# dsky_md_2_3v.net
KiCad netlist of a schematic drawn in EAGLE
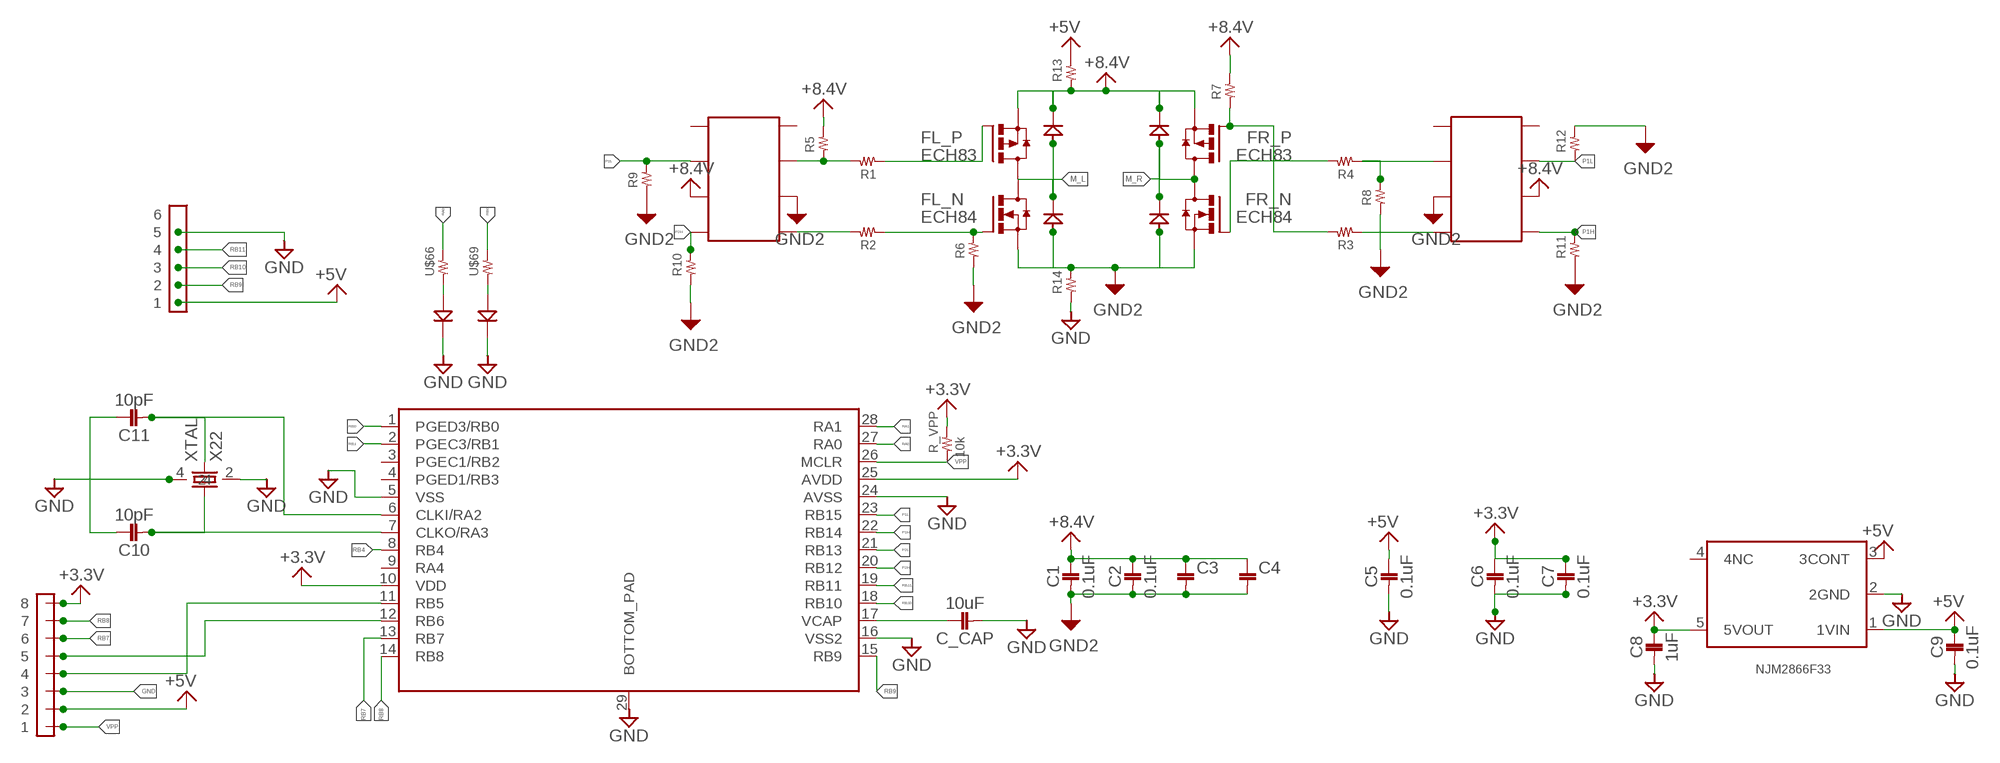
[diagram p0: schematic, sheet 1]

(export (version "E")
  (design (tool "Eeschema 10.0.6"))
  (components
    (comp (ref "C1")
      (value "0.1uF")
      (footprint "eagle-import:1608")
      (libsource (lib "eagle-import") (part "1608"))
    )
    (comp (ref "C2")
      (value "0.1uF")
      (footprint "eagle-import:1608")
      (libsource (lib "eagle-import") (part "1608"))
    )
    (comp (ref "C3")
      (value "2012")
      (footprint "eagle-import:2012")
      (libsource (lib "eagle-import") (part "2012"))
    )
    (comp (ref "C4")
      (value "2012")
      (footprint "eagle-import:2012")
      (libsource (lib "eagle-import") (part "2012"))
    )
    (comp (ref "C5")
      (value "0.1uF")
      (footprint "eagle-import:1608")
      (libsource (lib "eagle-import") (part "1608"))
    )
    (comp (ref "C6")
      (value "0.1uF")
      (footprint "eagle-import:1608")
      (libsource (lib "eagle-import") (part "1608"))
    )
    (comp (ref "C7")
      (value "0.1uF")
      (footprint "eagle-import:1608")
      (libsource (lib "eagle-import") (part "1608"))
    )
    (comp (ref "C8")
      (value "1uF")
      (footprint "eagle-import:1608")
      (libsource (lib "eagle-import") (part "1608"))
    )
    (comp (ref "C9")
      (value "0.1uF")
      (footprint "eagle-import:1608")
      (libsource (lib "eagle-import") (part "1608"))
    )
    (comp (ref "C10")
      (value "10pF")
      (footprint "eagle-import:1608")
      (libsource (lib "eagle-import") (part "1608"))
    )
    (comp (ref "C11")
      (value "10pF")
      (footprint "eagle-import:1608")
      (libsource (lib "eagle-import") (part "1608"))
    )
    (comp (ref "C_CAP")
      (value "10uF")
      (footprint "eagle-import:1608")
      (libsource (lib "eagle-import") (part "1608"))
    )
    (comp (ref "FL_N")
      (value "ECH84")
      (footprint "eagle-import:ECH8")
      (libsource (lib "eagle-import") (part "ECH84"))
    )
    (comp (ref "FL_P")
      (value "ECH83")
      (footprint "eagle-import:ECH8")
      (libsource (lib "eagle-import") (part "ECH83"))
    )
    (comp (ref "FR_N")
      (value "ECH84")
      (footprint "eagle-import:ECH8")
      (libsource (lib "eagle-import") (part "ECH84"))
    )
    (comp (ref "FR_P")
      (value "ECH83")
      (footprint "eagle-import:ECH8")
      (libsource (lib "eagle-import") (part "ECH83"))
    )
    (comp (ref "IC_L")
      (value "TC1427COA")
      (footprint "eagle-import:SOIC8")
      (libsource (lib "eagle-import") (part "TC1427COA"))
    )
    (comp (ref "IC_R")
      (value "TC1427COA")
      (footprint "eagle-import:SOIC8")
      (libsource (lib "eagle-import") (part "TC1427COA"))
    )
    (comp (ref "NJM2866F33")
      (value "TAR5SB")
      (footprint "eagle-import:SSOP5-P-0.95")
      (libsource (lib "eagle-import") (part "TAR5SB"))
    )
    (comp (ref "R1")
      (value "RESISTOR__SMD")
      (footprint "eagle-import:1608")
      (libsource (lib "eagle-import") (part "RESISTOR__SMD"))
    )
    (comp (ref "R2")
      (value "RESISTOR__SMD")
      (footprint "eagle-import:1608")
      (libsource (lib "eagle-import") (part "RESISTOR__SMD"))
    )
    (comp (ref "R3")
      (value "RESISTOR__SMD")
      (footprint "eagle-import:1608")
      (libsource (lib "eagle-import") (part "RESISTOR__SMD"))
    )
    (comp (ref "R4")
      (value "RESISTOR__SMD")
      (footprint "eagle-import:1608")
      (libsource (lib "eagle-import") (part "RESISTOR__SMD"))
    )
    (comp (ref "R5")
      (value "RESISTOR__SMD")
      (footprint "eagle-import:1608")
      (libsource (lib "eagle-import") (part "RESISTOR__SMD"))
    )
    (comp (ref "R6")
      (value "RESISTOR__SMD")
      (footprint "eagle-import:1608")
      (libsource (lib "eagle-import") (part "RESISTOR__SMD"))
    )
    (comp (ref "R7")
      (value "RESISTOR__SMD")
      (footprint "eagle-import:1608")
      (libsource (lib "eagle-import") (part "RESISTOR__SMD"))
    )
    (comp (ref "R8")
      (value "RESISTOR__SMD")
      (footprint "eagle-import:1608")
      (libsource (lib "eagle-import") (part "RESISTOR__SMD"))
    )
    (comp (ref "R9")
      (value "RESISTOR__SMD")
      (footprint "eagle-import:1608")
      (libsource (lib "eagle-import") (part "RESISTOR__SMD"))
    )
    (comp (ref "R10")
      (value "RESISTOR__SMD")
      (footprint "eagle-import:1608")
      (libsource (lib "eagle-import") (part "RESISTOR__SMD"))
    )
    (comp (ref "R11")
      (value "RESISTOR__SMD")
      (footprint "eagle-import:1608")
      (libsource (lib "eagle-import") (part "RESISTOR__SMD"))
    )
    (comp (ref "R12")
      (value "RESISTOR__SMD")
      (footprint "eagle-import:1608")
      (libsource (lib "eagle-import") (part "RESISTOR__SMD"))
    )
    (comp (ref "R13")
      (value "RESISTOR__SMD")
      (footprint "eagle-import:1608")
      (libsource (lib "eagle-import") (part "RESISTOR__SMD"))
    )
    (comp (ref "R14")
      (value "RESISTOR__SMD")
      (footprint "eagle-import:1608")
      (libsource (lib "eagle-import") (part "RESISTOR__SMD"))
    )
    (comp (ref "R_VPP")
      (value "10k")
      (footprint "eagle-import:1608")
      (libsource (lib "eagle-import") (part "RESISTOR__SMD"))
    )
    (comp (ref "U$3")
      (value "SS2040")
      (footprint "eagle-import:SOD-123FL")
      (libsource (lib "eagle-import") (part "SS2040"))
    )
    (comp (ref "U$5")
      (value "DSPIC33EP32MC202")
      (footprint "eagle-import:QFN-S28_6X6MC")
      (libsource (lib "eagle-import") (part "DSPIC33EP32MC202"))
    )
    (comp (ref "U$6")
      (value "1608")
      (footprint "eagle-import:1608")
      (libsource (lib "eagle-import") (part "LED_1608"))
    )
    (comp (ref "U$16")
      (value "1608")
      (footprint "eagle-import:1608")
      (libsource (lib "eagle-import") (part "LED_1608"))
    )
    (comp (ref "U$44")
      (value "FH12-6S-0.5")
      (footprint "eagle-import:FPC6")
      (libsource (lib "eagle-import") (part "FH12-6S-0.5"))
    )
    (comp (ref "U$66")
      (value "RESISTOR__SMD")
      (footprint "eagle-import:1608")
      (libsource (lib "eagle-import") (part "RESISTOR__SMD"))
    )
    (comp (ref "U$69")
      (value "RESISTOR__SMD")
      (footprint "eagle-import:1608")
      (libsource (lib "eagle-import") (part "RESISTOR__SMD"))
    )
    (comp (ref "U$70")
      (value "SS2040")
      (footprint "eagle-import:SOD-123FL")
      (libsource (lib "eagle-import") (part "SS2040"))
    )
    (comp (ref "U$71")
      (value "SS2040")
      (footprint "eagle-import:SOD-123FL")
      (libsource (lib "eagle-import") (part "SS2040"))
    )
    (comp (ref "U$73")
      (value "SS2040")
      (footprint "eagle-import:SOD-123FL")
      (libsource (lib "eagle-import") (part "SS2040"))
    )
    (comp (ref "U$80")
      (value "PIN_HEADER_8")
      (footprint "eagle-import:PIN_HEADER_8")
      (libsource (lib "eagle-import") (part "PIN_HEADER_8"))
    )
    (comp (ref "XTAL")
      (value "X22")
      (footprint "eagle-import:SMD_X22")
      (libsource (lib "eagle-import") (part "X22"))
    )
  )
  (nets
    (net (code "1") (name "+3.3V") (class "Default")
      (node (ref "C6") (pin "P$1") (pinfunction "1_P$1") (pintype "passive"))
      (node (ref "C7") (pin "P$1") (pinfunction "1_P$1") (pintype "passive"))
      (node (ref "C8") (pin "P$1") (pinfunction "1_P$1") (pintype "passive"))
      (node (ref "NJM2866F33") (pin "5") (pinfunction "5VOUT_5") (pintype "bidirectional"))
      (node (ref "R_VPP") (pin "2") (pinfunction "P$2_2") (pintype "passive"))
      (node (ref "U$5") (pin "10") (pinfunction "VDD_10") (pintype "bidirectional"))
      (node (ref "U$5") (pin "25") (pinfunction "AVDD_25") (pintype "bidirectional"))
      (node (ref "U$80") (pin "8") (pinfunction "8_8") (pintype "bidirectional"))
    )
    (net (code "2") (name "+5V") (class "Default")
      (node (ref "C5") (pin "P$1") (pinfunction "1_P$1") (pintype "passive"))
      (node (ref "C9") (pin "P$1") (pinfunction "1_P$1") (pintype "passive"))
      (node (ref "NJM2866F33") (pin "1") (pinfunction "1VIN_1") (pintype "bidirectional"))
      (node (ref "NJM2866F33") (pin "3") (pinfunction "3CONT_3") (pintype "bidirectional"))
      (node (ref "R13") (pin "2") (pinfunction "P$2_2") (pintype "passive"))
      (node (ref "U$44") (pin "P1") (pinfunction "1_P1") (pintype "bidirectional"))
      (node (ref "U$80") (pin "2") (pinfunction "2_2") (pintype "bidirectional"))
    )
    (net (code "3") (name "+8.4V") (class "Default")
      (node (ref "C1") (pin "P$1") (pinfunction "1_P$1") (pintype "passive"))
      (node (ref "C2") (pin "P$1") (pinfunction "1_P$1") (pintype "passive"))
      (node (ref "C3") (pin "1") (pinfunction "1_1") (pintype "passive"))
      (node (ref "C4") (pin "1") (pinfunction "1_1") (pintype "passive"))
      (node (ref "FL_P") (pin "1") (pinfunction "S_1") (pintype "passive"))
      (node (ref "FL_P") (pin "2") (pinfunction "S_2") (pintype "passive"))
      (node (ref "FL_P") (pin "3") (pinfunction "S_3") (pintype "passive"))
      (node (ref "FR_P") (pin "1") (pinfunction "S_1") (pintype "passive"))
      (node (ref "FR_P") (pin "2") (pinfunction "S_2") (pintype "passive"))
      (node (ref "FR_P") (pin "3") (pinfunction "S_3") (pintype "passive"))
      (node (ref "IC_L") (pin "3") (pinfunction "3_GND_3") (pintype "bidirectional"))
      (node (ref "IC_R") (pin "3") (pinfunction "3_GND_3") (pintype "bidirectional"))
      (node (ref "R13") (pin "1") (pinfunction "P$1_1") (pintype "passive"))
      (node (ref "R5") (pin "2") (pinfunction "P$2_2") (pintype "passive"))
      (node (ref "R7") (pin "2") (pinfunction "P$2_2") (pintype "passive"))
      (node (ref "U$70") (pin "2") (pinfunction "PK_2") (pintype "bidirectional"))
      (node (ref "U$73") (pin "2") (pinfunction "PK_2") (pintype "bidirectional"))
    )
    (net (code "4") (name "GND") (class "Default")
      (node (ref "C10") (pin "P$1") (pinfunction "1_P$1") (pintype "passive"))
      (node (ref "C11") (pin "P$1") (pinfunction "1_P$1") (pintype "passive"))
      (node (ref "C5") (pin "P$2") (pinfunction "2_P$2") (pintype "passive"))
      (node (ref "C6") (pin "P$2") (pinfunction "2_P$2") (pintype "passive"))
      (node (ref "C7") (pin "P$2") (pinfunction "2_P$2") (pintype "passive"))
      (node (ref "C8") (pin "P$2") (pinfunction "2_P$2") (pintype "passive"))
      (node (ref "C9") (pin "P$2") (pinfunction "2_P$2") (pintype "passive"))
      (node (ref "C_CAP") (pin "P$2") (pinfunction "2_P$2") (pintype "passive"))
      (node (ref "NJM2866F33") (pin "2") (pinfunction "2GND_2") (pintype "bidirectional"))
      (node (ref "R14") (pin "1") (pinfunction "P$1_1") (pintype "passive"))
      (node (ref "U$16") (pin "2") (pinfunction "K_2") (pintype "bidirectional"))
      (node (ref "U$44") (pin "P5") (pinfunction "5_P5") (pintype "bidirectional"))
      (node (ref "U$44") (pin "P_NC1") (pinfunction "5_P_NC1") (pintype "bidirectional"))
      (node (ref "U$44") (pin "P_NC2") (pinfunction "5_P_NC2") (pintype "bidirectional"))
      (node (ref "U$5") (pin "16") (pinfunction "VSS2_16") (pintype "power_in"))
      (node (ref "U$5") (pin "24") (pinfunction "AVSS_24") (pintype "bidirectional"))
      (node (ref "U$5") (pin "29") (pinfunction "BOTTOM_PAD_29") (pintype "bidirectional"))
      (node (ref "U$5") (pin "5") (pinfunction "VSS_5") (pintype "power_in"))
      (node (ref "U$6") (pin "2") (pinfunction "K_2") (pintype "bidirectional"))
      (node (ref "U$80") (pin "3") (pinfunction "3_3") (pintype "bidirectional"))
      (node (ref "XTAL") (pin "2") (pinfunction "2_2") (pintype "bidirectional"))
      (node (ref "XTAL") (pin "4") (pinfunction "4_4") (pintype "bidirectional"))
    )
    (net (code "5") (name "GND2") (class "Default")
      (node (ref "C1") (pin "P$2") (pinfunction "2_P$2") (pintype "passive"))
      (node (ref "C2") (pin "P$2") (pinfunction "2_P$2") (pintype "passive"))
      (node (ref "C3") (pin "2") (pinfunction "2_2") (pintype "passive"))
      (node (ref "C4") (pin "2") (pinfunction "2_2") (pintype "passive"))
      (node (ref "FL_N") (pin "1") (pinfunction "S_1") (pintype "passive"))
      (node (ref "FL_N") (pin "2") (pinfunction "S_2") (pintype "passive"))
      (node (ref "FL_N") (pin "3") (pinfunction "S_3") (pintype "passive"))
      (node (ref "FR_N") (pin "1") (pinfunction "S_1") (pintype "passive"))
      (node (ref "FR_N") (pin "2") (pinfunction "S_2") (pintype "passive"))
      (node (ref "FR_N") (pin "3") (pinfunction "S_3") (pintype "passive"))
      (node (ref "IC_L") (pin "6") (pinfunction "6_VDD_6") (pintype "bidirectional"))
      (node (ref "IC_R") (pin "6") (pinfunction "6_VDD_6") (pintype "bidirectional"))
      (node (ref "R10") (pin "1") (pinfunction "P$1_1") (pintype "passive"))
      (node (ref "R11") (pin "1") (pinfunction "P$1_1") (pintype "passive"))
      (node (ref "R12") (pin "2") (pinfunction "P$2_2") (pintype "passive"))
      (node (ref "R14") (pin "2") (pinfunction "P$2_2") (pintype "passive"))
      (node (ref "R6") (pin "1") (pinfunction "P$1_1") (pintype "passive"))
      (node (ref "R8") (pin "1") (pinfunction "P$1_1") (pintype "passive"))
      (node (ref "R9") (pin "1") (pinfunction "P$1_1") (pintype "passive"))
      (node (ref "U$3") (pin "1") (pinfunction "PA_1") (pintype "bidirectional"))
      (node (ref "U$71") (pin "1") (pinfunction "PA_1") (pintype "bidirectional"))
    )
    (net (code "6") (name "M_L") (class "Default")
      (node (ref "FL_N") (pin "5") (pinfunction "D_5") (pintype "passive"))
      (node (ref "FL_N") (pin "6") (pinfunction "D_6") (pintype "passive"))
      (node (ref "FL_N") (pin "7") (pinfunction "D_7") (pintype "passive"))
      (node (ref "FL_N") (pin "8") (pinfunction "D_8") (pintype "passive"))
      (node (ref "FL_P") (pin "5") (pinfunction "D_5") (pintype "passive"))
      (node (ref "FL_P") (pin "6") (pinfunction "D_6") (pintype "passive"))
      (node (ref "FL_P") (pin "7") (pinfunction "D_7") (pintype "passive"))
      (node (ref "FL_P") (pin "8") (pinfunction "D_8") (pintype "passive"))
      (node (ref "U$3") (pin "2") (pinfunction "PK_2") (pintype "bidirectional"))
      (node (ref "U$70") (pin "1") (pinfunction "PA_1") (pintype "bidirectional"))
    )
    (net (code "7") (name "M_R") (class "Default")
      (node (ref "FR_N") (pin "5") (pinfunction "D_5") (pintype "passive"))
      (node (ref "FR_N") (pin "6") (pinfunction "D_6") (pintype "passive"))
      (node (ref "FR_N") (pin "7") (pinfunction "D_7") (pintype "passive"))
      (node (ref "FR_N") (pin "8") (pinfunction "D_8") (pintype "passive"))
      (node (ref "FR_P") (pin "5") (pinfunction "D_5") (pintype "passive"))
      (node (ref "FR_P") (pin "6") (pinfunction "D_6") (pintype "passive"))
      (node (ref "FR_P") (pin "7") (pinfunction "D_7") (pintype "passive"))
      (node (ref "FR_P") (pin "8") (pinfunction "D_8") (pintype "passive"))
      (node (ref "U$71") (pin "2") (pinfunction "PK_2") (pintype "bidirectional"))
      (node (ref "U$73") (pin "1") (pinfunction "PA_1") (pintype "bidirectional"))
    )
    (net (code "8") (name "Net-(C10-2)") (class "Default")
      (node (ref "C10") (pin "P$2") (pinfunction "2_P$2") (pintype "passive"))
      (node (ref "U$5") (pin "7") (pinfunction "CLKO/RA3_7") (pintype "bidirectional"))
      (node (ref "XTAL") (pin "1") (pinfunction "1_1") (pintype "passive"))
    )
    (net (code "9") (name "Net-(C11-2)") (class "Default")
      (node (ref "C11") (pin "P$2") (pinfunction "2_P$2") (pintype "passive"))
      (node (ref "U$5") (pin "6") (pinfunction "CLKI/RA2_6") (pintype "bidirectional"))
      (node (ref "XTAL") (pin "3") (pinfunction "3_3") (pintype "passive"))
    )
    (net (code "10") (name "Net-(C_CAP-1)") (class "Default")
      (node (ref "C_CAP") (pin "P$1") (pinfunction "1_P$1") (pintype "passive"))
      (node (ref "U$5") (pin "17") (pinfunction "VCAP_17") (pintype "bidirectional"))
    )
    (net (code "11") (name "Net-(FL_N-G)") (class "Default")
      (node (ref "FL_N") (pin "4") (pinfunction "G_4") (pintype "passive"))
      (node (ref "R2") (pin "1") (pinfunction "P$1_1") (pintype "passive"))
      (node (ref "R6") (pin "2") (pinfunction "P$2_2") (pintype "passive"))
    )
    (net (code "12") (name "Net-(FL_P-G)") (class "Default")
      (node (ref "FL_P") (pin "4") (pinfunction "G_4") (pintype "passive"))
      (node (ref "R1") (pin "1") (pinfunction "P$1_1") (pintype "passive"))
    )
    (net (code "13") (name "Net-(FR_N-G)") (class "Default")
      (node (ref "FR_N") (pin "4") (pinfunction "G_4") (pintype "passive"))
      (node (ref "R4") (pin "2") (pinfunction "P$2_2") (pintype "passive"))
    )
    (net (code "14") (name "Net-(FR_P-G)") (class "Default")
      (node (ref "FR_P") (pin "4") (pinfunction "G_4") (pintype "passive"))
      (node (ref "R3") (pin "2") (pinfunction "P$2_2") (pintype "passive"))
      (node (ref "R7") (pin "1") (pinfunction "P$1_1") (pintype "passive"))
    )
    (net (code "15") (name "Net-(IC_L-5_OUT_B)") (class "Default")
      (node (ref "IC_L") (pin "5") (pinfunction "5_OUT_B_5") (pintype "bidirectional"))
      (node (ref "R2") (pin "2") (pinfunction "P$2_2") (pintype "passive"))
    )
    (net (code "16") (name "Net-(IC_L-7_OUT_A)") (class "Default")
      (node (ref "IC_L") (pin "7") (pinfunction "7_OUT_A_7") (pintype "bidirectional"))
      (node (ref "R1") (pin "2") (pinfunction "P$2_2") (pintype "passive"))
      (node (ref "R5") (pin "1") (pinfunction "P$1_1") (pintype "passive"))
    )
    (net (code "17") (name "Net-(IC_R-5_OUT_B)") (class "Default")
      (node (ref "IC_R") (pin "5") (pinfunction "5_OUT_B_5") (pintype "bidirectional"))
      (node (ref "R3") (pin "1") (pinfunction "P$1_1") (pintype "passive"))
    )
    (net (code "18") (name "Net-(IC_R-7_OUT_A)") (class "Default")
      (node (ref "IC_R") (pin "7") (pinfunction "7_OUT_A_7") (pintype "bidirectional"))
      (node (ref "R4") (pin "1") (pinfunction "P$1_1") (pintype "passive"))
      (node (ref "R8") (pin "2") (pinfunction "P$2_2") (pintype "passive"))
    )
    (net (code "19") (name "Net-(U$5-RB5)") (class "Default")
      (node (ref "U$5") (pin "11") (pinfunction "RB5_11") (pintype "bidirectional"))
      (node (ref "U$80") (pin "4") (pinfunction "4_4") (pintype "bidirectional"))
    )
    (net (code "20") (name "Net-(U$5-RB6)") (class "Default")
      (node (ref "U$5") (pin "12") (pinfunction "RB6_12") (pintype "bidirectional"))
      (node (ref "U$80") (pin "5") (pinfunction "5_5") (pintype "bidirectional"))
    )
    (net (code "21") (name "Net-(U$6-A)") (class "Default")
      (node (ref "U$6") (pin "1") (pinfunction "A_1") (pintype "bidirectional"))
      (node (ref "U$66") (pin "1") (pinfunction "P$1_1") (pintype "passive"))
    )
    (net (code "22") (name "Net-(U$16-A)") (class "Default")
      (node (ref "U$16") (pin "1") (pinfunction "A_1") (pintype "bidirectional"))
      (node (ref "U$69") (pin "1") (pinfunction "P$1_1") (pintype "passive"))
    )
    (net (code "23") (name "P1H") (class "Default")
      (node (ref "IC_R") (pin "4") (pinfunction "4_IN_B_4") (pintype "bidirectional"))
      (node (ref "R11") (pin "2") (pinfunction "P$2_2") (pintype "passive"))
      (node (ref "U$5") (pin "22") (pinfunction "RB14_22") (pintype "bidirectional"))
    )
    (net (code "24") (name "P1L") (class "Default")
      (node (ref "IC_R") (pin "2") (pinfunction "2_IN_A_2") (pintype "bidirectional"))
      (node (ref "R12") (pin "1") (pinfunction "P$1_1") (pintype "passive"))
      (node (ref "U$5") (pin "23") (pinfunction "RB15_23") (pintype "bidirectional"))
    )
    (net (code "25") (name "P2H") (class "Default")
      (node (ref "IC_L") (pin "4") (pinfunction "4_IN_B_4") (pintype "bidirectional"))
      (node (ref "R10") (pin "2") (pinfunction "P$2_2") (pintype "passive"))
      (node (ref "U$5") (pin "20") (pinfunction "RB12_20") (pintype "bidirectional"))
    )
    (net (code "26") (name "P2L") (class "Default")
      (node (ref "IC_L") (pin "2") (pinfunction "2_IN_A_2") (pintype "bidirectional"))
      (node (ref "R9") (pin "2") (pinfunction "P$2_2") (pintype "passive"))
      (node (ref "U$5") (pin "21") (pinfunction "RB13_21") (pintype "bidirectional"))
    )
    (net (code "27") (name "RA0") (class "Default")
      (node (ref "U$5") (pin "27") (pinfunction "RA0_27") (pintype "bidirectional"))
      (node (ref "U$66") (pin "2") (pinfunction "P$2_2") (pintype "passive"))
    )
    (net (code "28") (name "RA1") (class "Default")
      (node (ref "U$5") (pin "28") (pinfunction "RA1_28") (pintype "bidirectional"))
    )
    (net (code "29") (name "RB0") (class "Default")
      (node (ref "U$5") (pin "1") (pinfunction "PGED3/RB0_1") (pintype "bidirectional"))
      (node (ref "U$69") (pin "2") (pinfunction "P$2_2") (pintype "passive"))
    )
    (net (code "30") (name "RB1") (class "Default")
      (node (ref "U$5") (pin "2") (pinfunction "PGEC3/RB1_2") (pintype "bidirectional"))
    )
    (net (code "31") (name "RB4") (class "Default")
      (node (ref "U$5") (pin "8") (pinfunction "RB4_8") (pintype "bidirectional"))
    )
    (net (code "32") (name "RB7") (class "Default")
      (node (ref "U$5") (pin "13") (pinfunction "RB7_13") (pintype "bidirectional"))
      (node (ref "U$80") (pin "6") (pinfunction "6_6") (pintype "bidirectional"))
    )
    (net (code "33") (name "RB8") (class "Default")
      (node (ref "U$5") (pin "14") (pinfunction "RB8_14") (pintype "bidirectional"))
      (node (ref "U$80") (pin "7") (pinfunction "7_7") (pintype "bidirectional"))
    )
    (net (code "34") (name "RB9") (class "Default")
      (node (ref "U$44") (pin "P2") (pinfunction "2_P2") (pintype "bidirectional"))
      (node (ref "U$5") (pin "15") (pinfunction "RB9_15") (pintype "bidirectional"))
    )
    (net (code "35") (name "RB10") (class "Default")
      (node (ref "U$44") (pin "P3") (pinfunction "3_P3") (pintype "bidirectional"))
      (node (ref "U$5") (pin "18") (pinfunction "RB10_18") (pintype "bidirectional"))
    )
    (net (code "36") (name "RB11") (class "Default")
      (node (ref "U$44") (pin "P4") (pinfunction "4_P4") (pintype "bidirectional"))
      (node (ref "U$5") (pin "19") (pinfunction "RB11_19") (pintype "bidirectional"))
    )
    (net (code "37") (name "VPP") (class "Default")
      (node (ref "R_VPP") (pin "1") (pinfunction "P$1_1") (pintype "passive"))
      (node (ref "U$5") (pin "26") (pinfunction "MCLR_26") (pintype "bidirectional"))
      (node (ref "U$80") (pin "1") (pinfunction "1_1") (pintype "bidirectional"))
    )
    (net (code "38") (name "unconnected-(IC_L-1_NC-Pad1)") (class "Default")
      (node (ref "IC_L") (pin "1") (pinfunction "1_NC_1") (pintype "bidirectional"))
    )
    (net (code "39") (name "unconnected-(IC_L-8_NC-Pad8)") (class "Default")
      (node (ref "IC_L") (pin "8") (pinfunction "8_NC_8") (pintype "bidirectional"))
    )
    (net (code "40") (name "unconnected-(IC_R-1_NC-Pad1)") (class "Default")
      (node (ref "IC_R") (pin "1") (pinfunction "1_NC_1") (pintype "bidirectional"))
    )
    (net (code "41") (name "unconnected-(IC_R-8_NC-Pad8)") (class "Default")
      (node (ref "IC_R") (pin "8") (pinfunction "8_NC_8") (pintype "bidirectional"))
    )
    (net (code "42") (name "unconnected-(NJM2866F33-4NC-Pad4)") (class "Default")
      (node (ref "NJM2866F33") (pin "4") (pinfunction "4NC_4") (pintype "bidirectional"))
    )
    (net (code "43") (name "unconnected-(U$5-PGEC1{slash}RB2-Pad3)") (class "Default")
      (node (ref "U$5") (pin "3") (pinfunction "PGEC1/RB2_3") (pintype "bidirectional"))
    )
    (net (code "44") (name "unconnected-(U$5-PGED1{slash}RB3-Pad4)") (class "Default")
      (node (ref "U$5") (pin "4") (pinfunction "PGED1/RB3_4") (pintype "bidirectional"))
    )
    (net (code "45") (name "unconnected-(U$5-RA4-Pad9)") (class "Default")
      (node (ref "U$5") (pin "9") (pinfunction "RA4_9") (pintype "bidirectional"))
    )
    (net (code "46") (name "unconnected-(U$44-6-PadP6)") (class "Default")
      (node (ref "U$44") (pin "P6") (pinfunction "6_P6") (pintype "bidirectional"))
    )
  )
)
